# SENTINEL.net
KiCad netlist of a schematic drawn in EAGLE
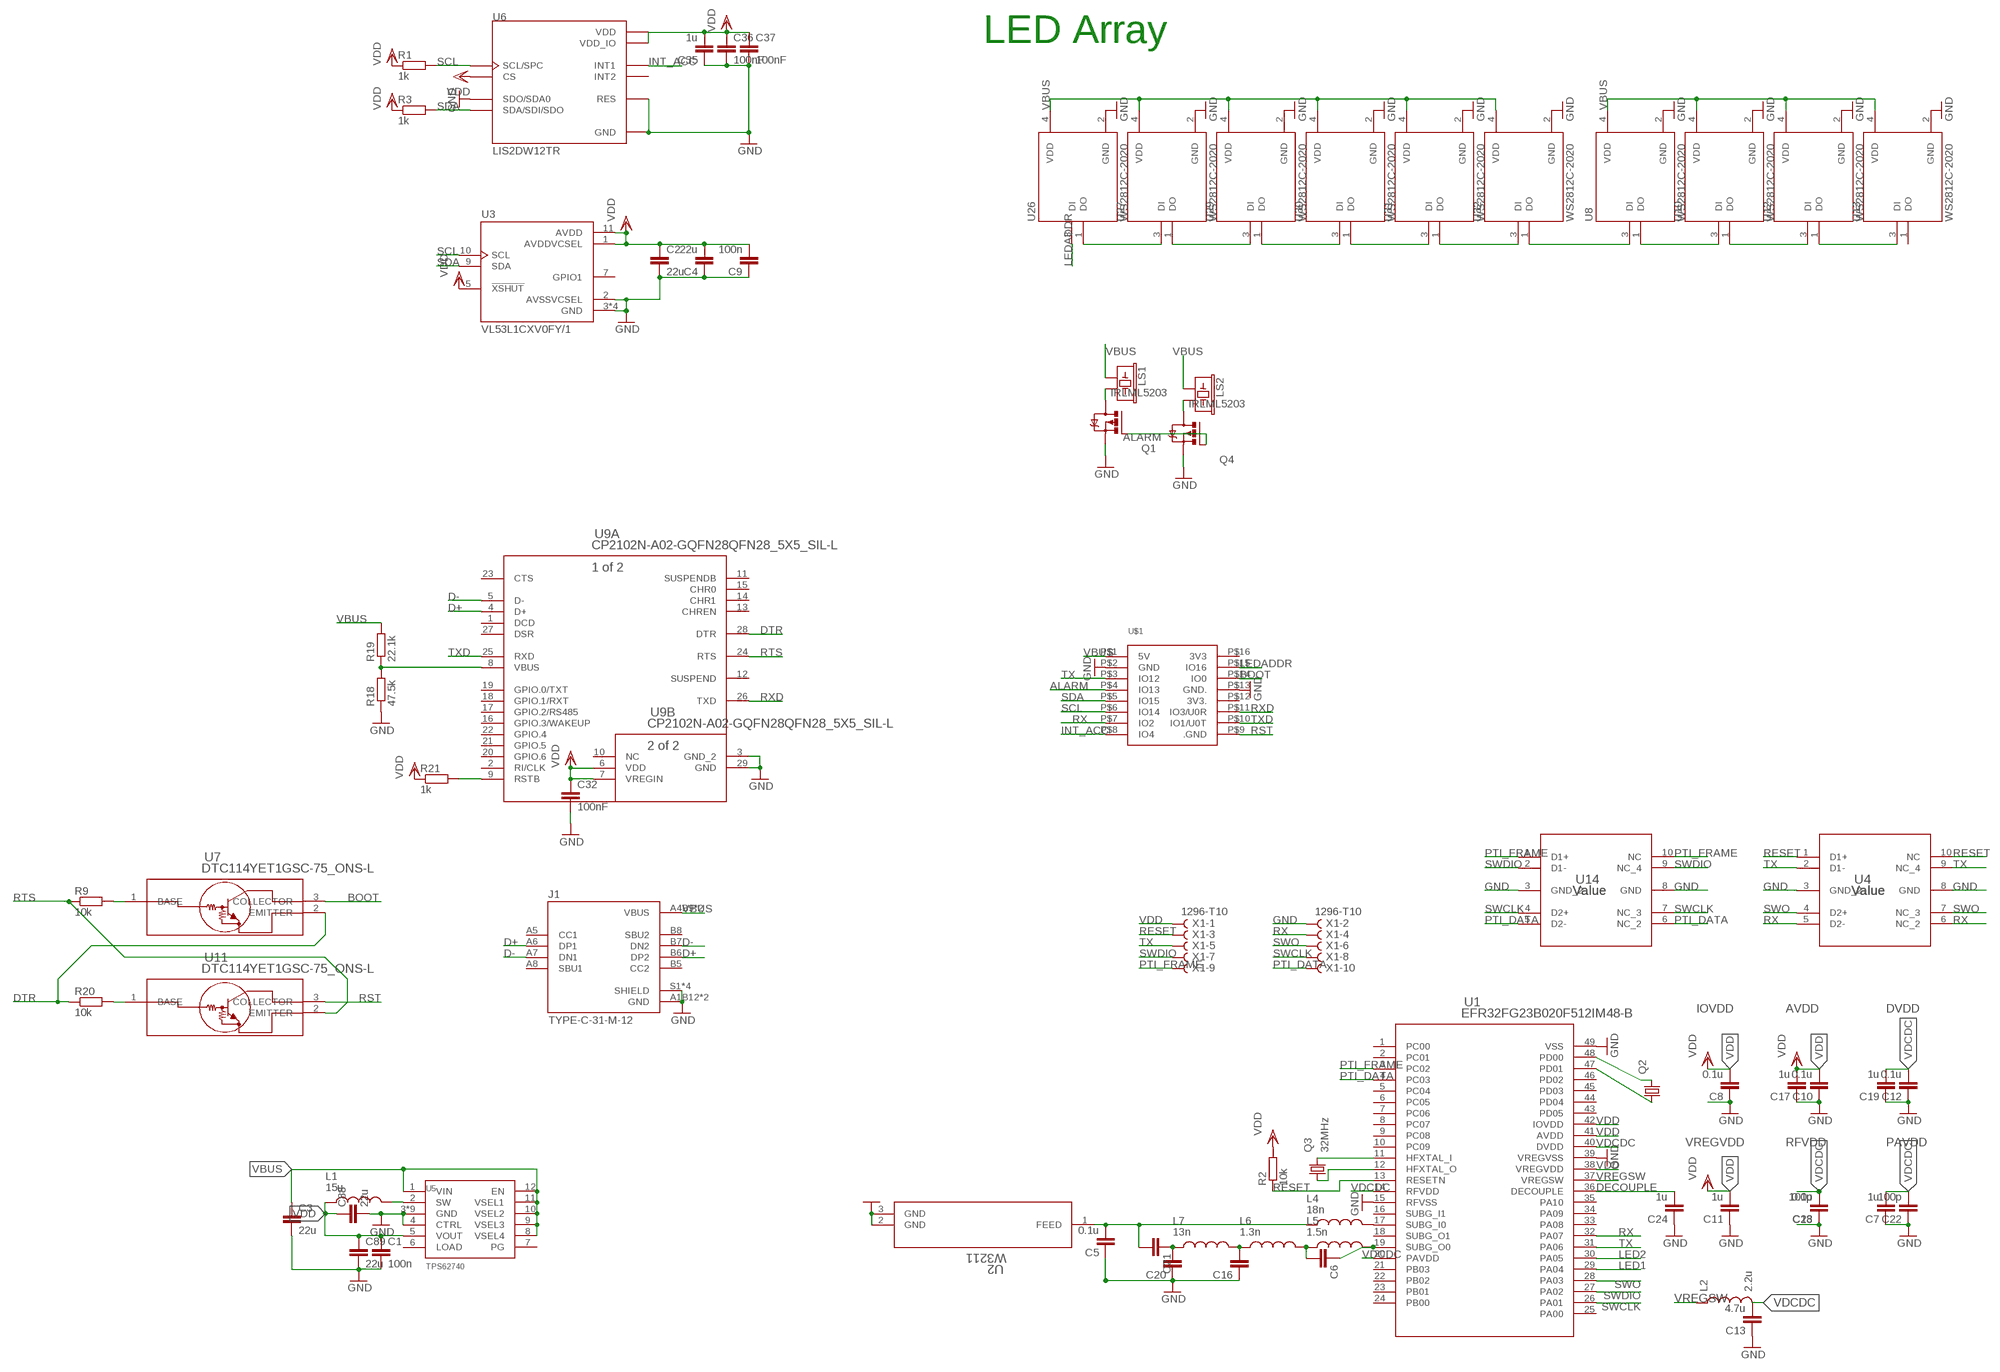
[diagram p0: schematic, sheet 1]

(export (version "E")
  (design (tool "Eeschema 10.0.6"))
  (components
    (comp (ref "C1")
      (value "100n")
      (footprint "eagle-import:C0402")
      (libsource (lib "eagle-import") (part "CC0402"))
    )
    (comp (ref "C2")
      (value "22u")
      (footprint "eagle-import:C0603R")
      (libsource (lib "eagle-import") (part "CC0603R"))
    )
    (comp (ref "C3")
      (value "22u")
      (footprint "eagle-import:C0603R")
      (libsource (lib "eagle-import") (part "CC0603R"))
    )
    (comp (ref "C4")
      (value "22u")
      (footprint "eagle-import:C0603R")
      (libsource (lib "eagle-import") (part "CC0603R"))
    )
    (comp (ref "C5")
      (value "0.1u")
      (footprint "eagle-import:C0402")
      (libsource (lib "eagle-import") (part "CC0402"))
    )
    (comp (ref "C6")
      (value "1.9p")
      (footprint "eagle-import:C0402")
      (libsource (lib "eagle-import") (part "CC0402"))
    )
    (comp (ref "C7")
      (value "1u")
      (footprint "eagle-import:C0402")
      (libsource (lib "eagle-import") (part "CC0402"))
    )
    (comp (ref "C8")
      (value "0.1u")
      (footprint "eagle-import:C0402")
      (libsource (lib "eagle-import") (part "CC0402"))
    )
    (comp (ref "C9")
      (value "100n")
      (footprint "eagle-import:C0402")
      (libsource (lib "eagle-import") (part "CC0402"))
    )
    (comp (ref "C10")
      (value "0.1u")
      (footprint "eagle-import:C0402")
      (libsource (lib "eagle-import") (part "CC0402"))
    )
    (comp (ref "C11")
      (value "1u")
      (footprint "eagle-import:C0402")
      (libsource (lib "eagle-import") (part "CC0402"))
    )
    (comp (ref "C12")
      (value "0.1u")
      (footprint "eagle-import:C0402")
      (libsource (lib "eagle-import") (part "CC0402"))
    )
    (comp (ref "C13")
      (value "4.7u")
      (footprint "eagle-import:C0603R")
      (libsource (lib "eagle-import") (part "CC0603R"))
    )
    (comp (ref "C16")
      (value "7.2p")
      (footprint "eagle-import:C0402")
      (libsource (lib "eagle-import") (part "CC0402"))
    )
    (comp (ref "C17")
      (value "1u")
      (footprint "eagle-import:C0402")
      (libsource (lib "eagle-import") (part "CC0402"))
    )
    (comp (ref "C18")
      (value "0.1u")
      (footprint "eagle-import:C0402")
      (libsource (lib "eagle-import") (part "CC0402"))
    )
    (comp (ref "C19")
      (value "1u")
      (footprint "eagle-import:C0402")
      (libsource (lib "eagle-import") (part "CC0402"))
    )
    (comp (ref "C20")
      (value "1.3p")
      (footprint "eagle-import:C0402")
      (libsource (lib "eagle-import") (part "CC0402"))
    )
    (comp (ref "C21")
      (value "220p")
      (footprint "eagle-import:C0402")
      (libsource (lib "eagle-import") (part "CC0402"))
    )
    (comp (ref "C22")
      (value "100p")
      (footprint "eagle-import:C0402")
      (libsource (lib "eagle-import") (part "CC0402"))
    )
    (comp (ref "C23")
      (value "100p")
      (footprint "eagle-import:C0402")
      (libsource (lib "eagle-import") (part "CC0402"))
    )
    (comp (ref "C24")
      (value "1u")
      (footprint "eagle-import:C0402")
      (libsource (lib "eagle-import") (part "CC0402"))
    )
    (comp (ref "C32")
      (value "100nF")
      (footprint "eagle-import:C0402")
      (libsource (lib "eagle-import") (part "CC0402"))
    )
    (comp (ref "C35")
      (value "1u")
      (footprint "eagle-import:C0603R")
      (libsource (lib "eagle-import") (part "CC0603R"))
    )
    (comp (ref "C36")
      (value "100nF")
      (footprint "eagle-import:C0402")
      (libsource (lib "eagle-import") (part "CC0402"))
    )
    (comp (ref "C37")
      (value "100nF")
      (footprint "eagle-import:C0402")
      (libsource (lib "eagle-import") (part "CC0402"))
    )
    (comp (ref "C88")
      (value "22u")
      (footprint "eagle-import:C0603R")
      (libsource (lib "eagle-import") (part "CC0603R"))
    )
    (comp (ref "C89")
      (value "22u")
      (footprint "eagle-import:C0603R")
      (libsource (lib "eagle-import") (part "CC0603R"))
    )
    (comp (ref "J1")
      (value "TYPE-C-31-M-12")
      (footprint "eagle-import:HRO_TYPE-C-31-M-12")
      (fields (field (name "MF") "HRO Electronics Co., Ltd."))
      (libsource (lib "eagle-import") (part "TYPE-C-31-M-12"))
    )
    (comp (ref "L1")
      (value "15u")
      (footprint "eagle-import:INDC3225X120N")
      (fields (field (name "MF") "Murata") (field (name "MP") "1277AS-H-1R5M=P2"))
      (libsource (lib "eagle-import") (part "1277AS-H-1R5M=P2"))
    )
    (comp (ref "L2")
      (value "2.2u")
      (footprint "eagle-import:L0603")
      (libsource (lib "eagle-import") (part "INDUCTOR"))
    )
    (comp (ref "L4")
      (value "18n")
      (footprint "eagle-import:INDC0402X26N")
      (fields (field (name "MF") "TDK") (field (name "MP") "MHQ0402P7N5JT000"))
      (libsource (lib "eagle-import") (part "MHQ0402P7N5JT000"))
    )
    (comp (ref "L5")
      (value "1.5n")
      (footprint "eagle-import:INDC0402X26N")
      (fields (field (name "MF") "TDK") (field (name "MP") "MHQ0402P7N5JT000"))
      (libsource (lib "eagle-import") (part "MHQ0402P7N5JT000"))
    )
    (comp (ref "L6")
      (value "1.3n")
      (footprint "eagle-import:INDC0402X26N")
      (fields (field (name "MF") "TDK") (field (name "MP") "MHQ0402P7N5JT000"))
      (libsource (lib "eagle-import") (part "MHQ0402P7N5JT000"))
    )
    (comp (ref "L7")
      (value "13n")
      (footprint "eagle-import:INDC0402X26N")
      (fields (field (name "MF") "TDK") (field (name "MP") "MHQ0402P7N5JT000"))
      (libsource (lib "eagle-import") (part "MHQ0402P7N5JT000"))
    )
    (comp (ref "LS1")
      (value "BUZZER-PTH_KIT")
      (footprint "eagle-import:BUZZER-12MM-KIT")
      (libsource (lib "eagle-import") (part "BUZZER-PTH_KIT"))
    )
    (comp (ref "LS2")
      (value "BUZZER-PTH_KIT")
      (footprint "eagle-import:BUZZER-12MM-KIT")
      (libsource (lib "eagle-import") (part "BUZZER-PTH_KIT"))
    )
    (comp (ref "Q1")
      (value "IRLML5203")
      (footprint "eagle-import:MICRO3")
      (libsource (lib "eagle-import") (part "IRLML5203"))
    )
    (comp (ref "Q2")
      (value "KX-327-RT")
      (footprint "eagle-import:2.0X1.2")
      (libsource (lib "eagle-import") (part "KX-327-RT"))
    )
    (comp (ref "Q3")
      (value "32MHz")
      (footprint "eagle-import:2.0X1.6_KX-5")
      (libsource (lib "eagle-import") (part "KX-5"))
    )
    (comp (ref "Q4")
      (value "IRLML5203")
      (footprint "eagle-import:MICRO3")
      (libsource (lib "eagle-import") (part "IRLML5203"))
    )
    (comp (ref "R1")
      (value "1k")
      (footprint "eagle-import:R0402")
      (libsource (lib "eagle-import") (part "RR0402"))
    )
    (comp (ref "R2")
      (value "10k")
      (footprint "eagle-import:R0402")
      (libsource (lib "eagle-import") (part "RR0402"))
    )
    (comp (ref "R3")
      (value "1k")
      (footprint "eagle-import:R0402")
      (libsource (lib "eagle-import") (part "RR0402"))
    )
    (comp (ref "R9")
      (value "10k")
      (footprint "eagle-import:R0402")
      (libsource (lib "eagle-import") (part "RR0402"))
    )
    (comp (ref "R18")
      (value "47.5k")
      (footprint "eagle-import:R0402")
      (libsource (lib "eagle-import") (part "RR0402"))
    )
    (comp (ref "R19")
      (value "22.1k")
      (footprint "eagle-import:R0402")
      (libsource (lib "eagle-import") (part "RR0402"))
    )
    (comp (ref "R20")
      (value "10k")
      (footprint "eagle-import:R0402")
      (libsource (lib "eagle-import") (part "RR0402"))
    )
    (comp (ref "R21")
      (value "1k")
      (footprint "eagle-import:R0402")
      (libsource (lib "eagle-import") (part "RR0402"))
    )
    (comp (ref "U$1")
      (value "ESP32-CAM")
      (footprint "eagle-import:ESP32-CAM")
      (fields (field (name "MF") "AI-Thinker"))
      (libsource (lib "eagle-import") (part "ESP32-CAM"))
    )
    (comp (ref "U1")
      (value "EFR32FG23B020F512IM48-B")
      (footprint "eagle-import:QFN_48_SIL")
      (fields (field (name "COPYRIGHT") "Copyright (C) 2022 Ultra Librarian. All rights reserved."))
      (libsource (lib "eagle-import") (part "EFR32FG23B020F512IM48-B"))
    )
    (comp (ref "U2")
      (value "W3211")
      (footprint "eagle-import:CHIP_3211_PUL")
      (fields (field (name "COPYRIGHT") "Copyright (C) 2022 Ultra Librarian. All rights reserved."))
      (libsource (lib "eagle-import") (part "W3211"))
    )
    (comp (ref "U3")
      (value "VL53L1CXV0FY/1")
      (footprint "eagle-import:SENSOR_VL53L1CXV0FY_1")
      (fields (field (name "MF") "STMicroelectronics"))
      (libsource (lib "eagle-import") (part "VL53L1CXV0FY/1"))
    )
    (comp (ref "U4")
      (value "Value")
      (footprint "eagle-import:DQA0010A")
      (fields (field (name "MANUFACTURER") "Texas Instruments") (field (name "PARTNUMBER") "ESD204DQAR"))
      (libsource (lib "eagle-import") (part "ESD204DQAR"))
    )
    (comp (ref "U5")
      (value "TPS62740")
      (footprint "eagle-import:DSS")
      (libsource (lib "eagle-import") (part "TPS62740"))
    )
    (comp (ref "U6")
      (value "LIS2DW12TR")
      (footprint "eagle-import:LGA12R50P4X4_200X200X70")
      (fields (field (name "MF") "STMicroelectronics"))
      (libsource (lib "eagle-import") (part "LIS2DW12TR"))
    )
    (comp (ref "U7")
      (value "DTC114YET1GSC-75_ONS-L")
      (footprint "eagle-import:SC-75_ONS-L")
      (fields
        (field (name "MANUFACTURER_PART_NUMBER") "DTC114YET1G")
        (field (name "COPYRIGHT") "Copyright (C) 2018 Accelerated Designs. All rights reserved")
      )
      (libsource (lib "eagle-import") (part "DTC114YET1GSC-75_ONS-L"))
    )
    (comp (ref "U8")
      (value "WS2812C-2020")
      (footprint "eagle-import:LED_WS2812C-2020")
      (fields (field (name "MF") "Worldsemi"))
      (libsource (lib "eagle-import") (part "WS2812C-2020"))
    )
    (comp (ref "U9")
      (value "CP2102N-A02-GQFN28QFN28_5X5_SIL-L")
      (footprint "eagle-import:QFN28_5X5_SIL-L")
      (fields
        (field (name "MANUFACTURER_PART_NUMBER") "CP2102N-A02-GQFN28")
        (field (name "COPYRIGHT") "Copyright (C) 2018 Accelerated Designs. All rights reserved")
      )
      (libsource (lib "eagle-import") (part "CP2102N-A02-GQFN28QFN28_5X5_SIL-L"))
    )
    (comp (ref "U10")
      (value "WS2812C-2020")
      (footprint "eagle-import:LED_WS2812C-2020")
      (fields (field (name "MF") "Worldsemi"))
      (libsource (lib "eagle-import") (part "WS2812C-2020"))
    )
    (comp (ref "U11")
      (value "DTC114YET1GSC-75_ONS-L")
      (footprint "eagle-import:SC-75_ONS-L")
      (fields
        (field (name "MANUFACTURER_PART_NUMBER") "DTC114YET1G")
        (field (name "COPYRIGHT") "Copyright (C) 2018 Accelerated Designs. All rights reserved")
      )
      (libsource (lib "eagle-import") (part "DTC114YET1GSC-75_ONS-L"))
    )
    (comp (ref "U12")
      (value "WS2812C-2020")
      (footprint "eagle-import:LED_WS2812C-2020")
      (fields (field (name "MF") "Worldsemi"))
      (libsource (lib "eagle-import") (part "WS2812C-2020"))
    )
    (comp (ref "U13")
      (value "WS2812C-2020")
      (footprint "eagle-import:LED_WS2812C-2020")
      (fields (field (name "MF") "Worldsemi"))
      (libsource (lib "eagle-import") (part "WS2812C-2020"))
    )
    (comp (ref "U14")
      (value "Value")
      (footprint "eagle-import:DQA0010A")
      (fields (field (name "MANUFACTURER") "Texas Instruments") (field (name "PARTNUMBER") "ESD204DQAR"))
      (libsource (lib "eagle-import") (part "ESD204DQAR"))
    )
    (comp (ref "U26")
      (value "WS2812C-2020")
      (footprint "eagle-import:LED_WS2812C-2020")
      (fields (field (name "MF") "Worldsemi"))
      (libsource (lib "eagle-import") (part "WS2812C-2020"))
    )
    (comp (ref "U27")
      (value "WS2812C-2020")
      (footprint "eagle-import:LED_WS2812C-2020")
      (fields (field (name "MF") "Worldsemi"))
      (libsource (lib "eagle-import") (part "WS2812C-2020"))
    )
    (comp (ref "U29")
      (value "WS2812C-2020")
      (footprint "eagle-import:LED_WS2812C-2020")
      (fields (field (name "MF") "Worldsemi"))
      (libsource (lib "eagle-import") (part "WS2812C-2020"))
    )
    (comp (ref "U30")
      (value "WS2812C-2020")
      (footprint "eagle-import:LED_WS2812C-2020")
      (fields (field (name "MF") "Worldsemi"))
      (libsource (lib "eagle-import") (part "WS2812C-2020"))
    )
    (comp (ref "U31")
      (value "WS2812C-2020")
      (footprint "eagle-import:LED_WS2812C-2020")
      (fields (field (name "MF") "Worldsemi"))
      (libsource (lib "eagle-import") (part "WS2812C-2020"))
    )
    (comp (ref "U32")
      (value "WS2812C-2020")
      (footprint "eagle-import:LED_WS2812C-2020")
      (fields (field (name "MF") "Worldsemi"))
      (libsource (lib "eagle-import") (part "WS2812C-2020"))
    )
    (comp (ref "X1")
      (value "1296-T10")
      (footprint "eagle-import:1296-10")
      (libsource (lib "eagle-import") (part "1296-T10"))
    )
  )
  (nets
    (net (code "1") (name "/ALARM") (class "Default")
      (node (ref "Q1") (pin "1") (pinfunction "G_1") (pintype "passive"))
      (node (ref "Q4") (pin "1") (pinfunction "G_1") (pintype "passive"))
      (node (ref "U$1") (pin "P$4") (pinfunction "IO13_P$4") (pintype "bidirectional"))
    )
    (net (code "2") (name "/BOOT") (class "Default")
      (node (ref "U$1") (pin "P$14") (pinfunction "IO0_P$14") (pintype "bidirectional"))
      (node (ref "U7") (pin "3") (pinfunction "COLLECTOR_3") (pintype "output"))
    )
    (net (code "3") (name "/D+") (class "Default")
      (node (ref "J1") (pin "A6") (pinfunction "DP1_A6") (pintype "bidirectional"))
      (node (ref "J1") (pin "B6") (pinfunction "DP2_B6") (pintype "bidirectional"))
      (node (ref "U9") (pin "4") (pinfunction "D+_4") (pintype "input"))
    )
    (net (code "4") (name "/D-") (class "Default")
      (node (ref "J1") (pin "A7") (pinfunction "DN1_A7") (pintype "bidirectional"))
      (node (ref "J1") (pin "B7") (pinfunction "DN2_B7") (pintype "bidirectional"))
      (node (ref "U9") (pin "5") (pinfunction "D-_5") (pintype "input"))
    )
    (net (code "5") (name "/DECOUPLE") (class "Default")
      (node (ref "C24") (pin "2") (pinfunction "2_2") (pintype "passive"))
      (node (ref "U1") (pin "36") (pinfunction "DECOUPLE_36") (pintype "passive"))
    )
    (net (code "6") (name "/DTR") (class "Default")
      (node (ref "R20") (pin "1") (pinfunction "1_1") (pintype "passive"))
      (node (ref "U7") (pin "2") (pinfunction "EMITTER_2") (pintype "passive"))
      (node (ref "U9") (pin "28") (pinfunction "DTR_28") (pintype "output"))
    )
    (net (code "7") (name "/INT_ACC") (class "Default")
      (node (ref "U$1") (pin "P$8") (pinfunction "IO4_P$8") (pintype "bidirectional"))
      (node (ref "U6") (pin "12") (pinfunction "INT1_12") (pintype "output"))
    )
    (net (code "8") (name "/LED1") (class "Default")
      (node (ref "U1") (pin "29") (pinfunction "PA04_29") (pintype "bidirectional"))
    )
    (net (code "9") (name "/LED2") (class "Default")
      (node (ref "U1") (pin "30") (pinfunction "PA05_30") (pintype "bidirectional"))
    )
    (net (code "10") (name "/LEDADDR") (class "Default")
      (node (ref "U$1") (pin "P$15") (pinfunction "IO16_P$15") (pintype "bidirectional"))
      (node (ref "U26") (pin "3") (pinfunction "DI_3") (pintype "input"))
    )
    (net (code "11") (name "/PTI_DATA") (class "Default")
      (node (ref "U1") (pin "4") (pinfunction "PC03_4") (pintype "bidirectional"))
      (node (ref "U14") (pin "5") (pinfunction "D2-_5") (pintype "bidirectional"))
      (node (ref "U14") (pin "6") (pinfunction "NC_2_6") (pintype "passive"))
      (node (ref "X1") (pin "10") (pinfunction "B_10") (pintype "passive"))
    )
    (net (code "12") (name "/PTI_FRAME") (class "Default")
      (node (ref "U1") (pin "3") (pinfunction "PC02_3") (pintype "bidirectional"))
      (node (ref "U14") (pin "1") (pinfunction "D1+_1") (pintype "bidirectional"))
      (node (ref "U14") (pin "10") (pinfunction "NC_10") (pintype "passive"))
      (node (ref "X1") (pin "9") (pinfunction "B_9") (pintype "passive"))
    )
    (net (code "13") (name "/RESET") (class "Default")
      (node (ref "R2") (pin "1") (pinfunction "1_1") (pintype "passive"))
      (node (ref "U1") (pin "13") (pinfunction "RESETN_13") (pintype "input"))
      (node (ref "U4") (pin "1") (pinfunction "D1+_1") (pintype "bidirectional"))
      (node (ref "U4") (pin "10") (pinfunction "NC_10") (pintype "passive"))
      (node (ref "X1") (pin "3") (pinfunction "B_3") (pintype "passive"))
    )
    (net (code "14") (name "/RST") (class "Default")
      (node (ref "U$1") (pin "P$9") (pinfunction ".GND_P$9") (pintype "bidirectional"))
      (node (ref "U11") (pin "3") (pinfunction "COLLECTOR_3") (pintype "output"))
    )
    (net (code "15") (name "/RTS") (class "Default")
      (node (ref "R9") (pin "1") (pinfunction "1_1") (pintype "passive"))
      (node (ref "U11") (pin "2") (pinfunction "EMITTER_2") (pintype "passive"))
      (node (ref "U9") (pin "24") (pinfunction "RTS_24") (pintype "output"))
    )
    (net (code "16") (name "/RX") (class "Default")
      (node (ref "U$1") (pin "P$7") (pinfunction "IO2_P$7") (pintype "bidirectional"))
      (node (ref "U1") (pin "32") (pinfunction "PA07_32") (pintype "bidirectional"))
      (node (ref "U4") (pin "5") (pinfunction "D2-_5") (pintype "bidirectional"))
      (node (ref "U4") (pin "6") (pinfunction "NC_2_6") (pintype "passive"))
      (node (ref "X1") (pin "4") (pinfunction "B_4") (pintype "passive"))
    )
    (net (code "17") (name "/RXD") (class "Default")
      (node (ref "U$1") (pin "P$11") (pinfunction "IO3/U0R_P$11") (pintype "bidirectional"))
      (node (ref "U9") (pin "26") (pinfunction "TXD_26") (pintype "output"))
    )
    (net (code "18") (name "/SCL") (class "Default")
      (node (ref "R1") (pin "2") (pinfunction "2_2") (pintype "passive"))
      (node (ref "U$1") (pin "P$6") (pinfunction "IO14_P$6") (pintype "bidirectional"))
      (node (ref "U3") (pin "10") (pinfunction "SCL_10") (pintype "input"))
      (node (ref "U6") (pin "1") (pinfunction "SCL/SPC_1") (pintype "input"))
    )
    (net (code "19") (name "/SDA") (class "Default")
      (node (ref "R3") (pin "2") (pinfunction "2_2") (pintype "passive"))
      (node (ref "U$1") (pin "P$5") (pinfunction "IO15_P$5") (pintype "bidirectional"))
      (node (ref "U3") (pin "9") (pinfunction "SDA_9") (pintype "bidirectional"))
      (node (ref "U6") (pin "4") (pinfunction "SDA/SDI/SDO_4") (pintype "bidirectional"))
    )
    (net (code "20") (name "/SWCLK") (class "Default")
      (node (ref "U1") (pin "26") (pinfunction "PA01_26") (pintype "bidirectional"))
      (node (ref "U14") (pin "4") (pinfunction "D2+_4") (pintype "bidirectional"))
      (node (ref "U14") (pin "7") (pinfunction "NC_3_7") (pintype "passive"))
      (node (ref "X1") (pin "8") (pinfunction "B_8") (pintype "passive"))
    )
    (net (code "21") (name "/SWDIO") (class "Default")
      (node (ref "U1") (pin "27") (pinfunction "PA02_27") (pintype "bidirectional"))
      (node (ref "U14") (pin "2") (pinfunction "D1-_2") (pintype "bidirectional"))
      (node (ref "U14") (pin "9") (pinfunction "NC_4_9") (pintype "passive"))
      (node (ref "X1") (pin "7") (pinfunction "B_7") (pintype "passive"))
    )
    (net (code "22") (name "/SWO") (class "Default")
      (node (ref "U1") (pin "28") (pinfunction "PA03_28") (pintype "bidirectional"))
      (node (ref "U4") (pin "4") (pinfunction "D2+_4") (pintype "bidirectional"))
      (node (ref "U4") (pin "7") (pinfunction "NC_3_7") (pintype "passive"))
      (node (ref "X1") (pin "6") (pinfunction "B_6") (pintype "passive"))
    )
    (net (code "23") (name "/TX") (class "Default")
      (node (ref "U$1") (pin "P$3") (pinfunction "IO12_P$3") (pintype "bidirectional"))
      (node (ref "U1") (pin "31") (pinfunction "PA06_31") (pintype "bidirectional"))
      (node (ref "U4") (pin "2") (pinfunction "D1-_2") (pintype "bidirectional"))
      (node (ref "U4") (pin "9") (pinfunction "NC_4_9") (pintype "passive"))
      (node (ref "X1") (pin "5") (pinfunction "B_5") (pintype "passive"))
    )
    (net (code "24") (name "/TXD") (class "Default")
      (node (ref "U$1") (pin "P$10") (pinfunction "IO1/U0T_P$10") (pintype "bidirectional"))
      (node (ref "U9") (pin "25") (pinfunction "RXD_25") (pintype "input"))
    )
    (net (code "25") (name "/VREGSW") (class "Default")
      (node (ref "L2") (pin "1") (pinfunction "1_1") (pintype "passive"))
      (node (ref "U1") (pin "37") (pinfunction "VREGSW_37") (pintype "power_in"))
    )
    (net (code "26") (name "GND") (class "Default")
      (node (ref "C1") (pin "2") (pinfunction "2_2") (pintype "passive"))
      (node (ref "C10") (pin "1") (pinfunction "1_1") (pintype "passive"))
      (node (ref "C11") (pin "1") (pinfunction "1_1") (pintype "passive"))
      (node (ref "C12") (pin "1") (pinfunction "1_1") (pintype "passive"))
      (node (ref "C13") (pin "1") (pinfunction "1_1") (pintype "passive"))
      (node (ref "C16") (pin "1") (pinfunction "1_1") (pintype "passive"))
      (node (ref "C17") (pin "1") (pinfunction "1_1") (pintype "passive"))
      (node (ref "C18") (pin "1") (pinfunction "1_1") (pintype "passive"))
      (node (ref "C19") (pin "1") (pinfunction "1_1") (pintype "passive"))
      (node (ref "C2") (pin "2") (pinfunction "2_2") (pintype "passive"))
      (node (ref "C20") (pin "1") (pinfunction "1_1") (pintype "passive"))
      (node (ref "C22") (pin "1") (pinfunction "1_1") (pintype "passive"))
      (node (ref "C23") (pin "1") (pinfunction "1_1") (pintype "passive"))
      (node (ref "C24") (pin "1") (pinfunction "1_1") (pintype "passive"))
      (node (ref "C3") (pin "2") (pinfunction "2_2") (pintype "passive"))
      (node (ref "C32") (pin "2") (pinfunction "2_2") (pintype "passive"))
      (node (ref "C35") (pin "1") (pinfunction "1_1") (pintype "passive"))
      (node (ref "C36") (pin "2") (pinfunction "2_2") (pintype "passive"))
      (node (ref "C37") (pin "2") (pinfunction "2_2") (pintype "passive"))
      (node (ref "C4") (pin "1") (pinfunction "1_1") (pintype "passive"))
      (node (ref "C5") (pin "1") (pinfunction "1_1") (pintype "passive"))
      (node (ref "C7") (pin "1") (pinfunction "1_1") (pintype "passive"))
      (node (ref "C8") (pin "1") (pinfunction "1_1") (pintype "passive"))
      (node (ref "C88") (pin "2") (pinfunction "2_2") (pintype "passive"))
      (node (ref "C89") (pin "2") (pinfunction "2_2") (pintype "passive"))
      (node (ref "C9") (pin "1") (pinfunction "1_1") (pintype "passive"))
      (node (ref "J1") (pin "A1B12") (pinfunction "GND_A1B12") (pintype "power_in"))
      (node (ref "J1") (pin "B1A12") (pinfunction "GND_B1A12") (pintype "power_in"))
      (node (ref "J1") (pin "S1") (pinfunction "SHIELD_S1") (pintype "passive"))
      (node (ref "J1") (pin "S2") (pinfunction "SHIELD_S2") (pintype "passive"))
      (node (ref "J1") (pin "S3") (pinfunction "SHIELD_S3") (pintype "passive"))
      (node (ref "J1") (pin "S4") (pinfunction "SHIELD_S4") (pintype "passive"))
      (node (ref "Q1") (pin "2") (pinfunction "S_2") (pintype "passive"))
      (node (ref "Q4") (pin "2") (pinfunction "S_2") (pintype "passive"))
      (node (ref "R18") (pin "1") (pinfunction "1_1") (pintype "passive"))
      (node (ref "U$1") (pin "P$13") (pinfunction "GND._P$13") (pintype "bidirectional"))
      (node (ref "U$1") (pin "P$2") (pinfunction "GND_P$2") (pintype "bidirectional"))
      (node (ref "U1") (pin "15") (pinfunction "RFVSS_15") (pintype "power_in"))
      (node (ref "U1") (pin "39") (pinfunction "VREGVSS_39") (pintype "power_in"))
      (node (ref "U1") (pin "49") (pinfunction "VSS_49") (pintype "power_in"))
      (node (ref "U10") (pin "2") (pinfunction "GND_2") (pintype "power_in"))
      (node (ref "U12") (pin "2") (pinfunction "GND_2") (pintype "power_in"))
      (node (ref "U13") (pin "2") (pinfunction "GND_2") (pintype "power_in"))
      (node (ref "U14") (pin "3") (pinfunction "GND_2_3") (pintype "power_in"))
      (node (ref "U14") (pin "8") (pinfunction "GND_8") (pintype "power_in"))
      (node (ref "U2") (pin "2") (pinfunction "GND_2") (pintype "passive"))
      (node (ref "U2") (pin "3") (pinfunction "GND_3") (pintype "passive"))
      (node (ref "U26") (pin "2") (pinfunction "GND_2") (pintype "power_in"))
      (node (ref "U27") (pin "2") (pinfunction "GND_2") (pintype "power_in"))
      (node (ref "U29") (pin "2") (pinfunction "GND_2") (pintype "power_in"))
      (node (ref "U3") (pin "12") (pinfunction "GND_12") (pintype "power_in"))
      (node (ref "U3") (pin "2") (pinfunction "AVSSVCSEL_2") (pintype "power_in"))
      (node (ref "U3") (pin "3") (pinfunction "GND_3") (pintype "power_in"))
      (node (ref "U3") (pin "4") (pinfunction "GND_4") (pintype "power_in"))
      (node (ref "U3") (pin "6") (pinfunction "GND_6") (pintype "power_in"))
      (node (ref "U30") (pin "2") (pinfunction "GND_2") (pintype "power_in"))
      (node (ref "U31") (pin "2") (pinfunction "GND_2") (pintype "power_in"))
      (node (ref "U32") (pin "2") (pinfunction "GND_2") (pintype "power_in"))
      (node (ref "U4") (pin "3") (pinfunction "GND_2_3") (pintype "power_in"))
      (node (ref "U4") (pin "8") (pinfunction "GND_8") (pintype "power_in"))
      (node (ref "U5") (pin "13") (pinfunction "GND_13") (pintype "bidirectional"))
      (node (ref "U5") (pin "14") (pinfunction "GND_14") (pintype "bidirectional"))
      (node (ref "U5") (pin "15") (pinfunction "GND_15") (pintype "bidirectional"))
      (node (ref "U5") (pin "16") (pinfunction "GND_16") (pintype "bidirectional"))
      (node (ref "U5") (pin "18") (pinfunction "GND_18") (pintype "bidirectional"))
      (node (ref "U5") (pin "19") (pinfunction "GND_19") (pintype "bidirectional"))
      (node (ref "U5") (pin "20") (pinfunction "GND_20") (pintype "bidirectional"))
      (node (ref "U5") (pin "3") (pinfunction "GND_3") (pintype "bidirectional"))
      (node (ref "U5") (pin "4") (pinfunction "CTRL_4") (pintype "bidirectional"))
      (node (ref "U5") (pin "P$18") (pinfunction "GND_P$18") (pintype "bidirectional"))
      (node (ref "U6") (pin "3") (pinfunction "SDO/SDA0_3") (pintype "bidirectional"))
      (node (ref "U6") (pin "6") (pinfunction "GND_6") (pintype "power_in"))
      (node (ref "U6") (pin "7") (pinfunction "RES_7") (pintype "passive"))
      (node (ref "U6") (pin "8") (pinfunction "GND_8") (pintype "power_in"))
      (node (ref "U8") (pin "2") (pinfunction "GND_2") (pintype "power_in"))
      (node (ref "U9") (pin "29") (pinfunction "GND_29") (pintype "passive"))
      (node (ref "U9") (pin "3") (pinfunction "GND_2_3") (pintype "passive"))
      (node (ref "X1") (pin "2") (pinfunction "B_2") (pintype "passive"))
    )
    (net (code "27") (name "Net-(C6-Pad2)") (class "Default")
      (node (ref "C6") (pin "2") (pinfunction "2_2") (pintype "passive"))
      (node (ref "L5") (pin "1") (pinfunction "1_1") (pintype "passive"))
      (node (ref "L6") (pin "2") (pinfunction "2_2") (pintype "passive"))
    )
    (net (code "28") (name "Net-(C16-Pad2)") (class "Default")
      (node (ref "C16") (pin "2") (pinfunction "2_2") (pintype "passive"))
      (node (ref "L6") (pin "1") (pinfunction "1_1") (pintype "passive"))
      (node (ref "L7") (pin "2") (pinfunction "2_2") (pintype "passive"))
    )
    (net (code "29") (name "Net-(C20-Pad2)") (class "Default")
      (node (ref "C20") (pin "2") (pinfunction "2_2") (pintype "passive"))
      (node (ref "C21") (pin "1") (pinfunction "1_1") (pintype "passive"))
      (node (ref "L7") (pin "1") (pinfunction "1_1") (pintype "passive"))
    )
    (net (code "30") (name "Net-(LS1-2)") (class "Default")
      (node (ref "LS1") (pin "-") (pinfunction "2_-") (pintype "passive"))
      (node (ref "Q1") (pin "3") (pinfunction "D_3") (pintype "passive"))
    )
    (net (code "31") (name "Net-(LS2-2)") (class "Default")
      (node (ref "LS2") (pin "-") (pinfunction "2_-") (pintype "passive"))
      (node (ref "Q4") (pin "3") (pinfunction "D_3") (pintype "passive"))
    )
    (net (code "32") (name "Net-(Q3-2)") (class "Default")
      (node (ref "Q3") (pin "3") (pinfunction "2_3") (pintype "passive"))
      (node (ref "U1") (pin "11") (pinfunction "HFXTAL_I_11") (pintype "input"))
    )
    (net (code "33") (name "Net-(U1-HFXTAL_O)") (class "Default")
      (node (ref "Q3") (pin "1") (pinfunction "1_1") (pintype "passive"))
      (node (ref "U1") (pin "12") (pinfunction "HFXTAL_O_12") (pintype "output"))
    )
    (net (code "34") (name "Net-(U1-PD00)") (class "Default")
      (node (ref "Q2") (pin "2") (pinfunction "2_2") (pintype "passive"))
      (node (ref "U1") (pin "48") (pinfunction "PD00_48") (pintype "bidirectional"))
    )
    (net (code "35") (name "Net-(U1-PD01)") (class "Default")
      (node (ref "Q2") (pin "1") (pinfunction "1_1") (pintype "passive"))
      (node (ref "U1") (pin "47") (pinfunction "PD01_47") (pintype "bidirectional"))
    )
    (net (code "36") (name "Net-(U1-SUBG_I0)") (class "Default")
      (node (ref "L4") (pin "2") (pinfunction "2_2") (pintype "passive"))
      (node (ref "U1") (pin "17") (pinfunction "SUBG_I0_17") (pintype "input"))
    )
    (net (code "37") (name "Net-(U1-SUBG_O0)") (class "Default")
      (node (ref "C6") (pin "1") (pinfunction "1_1") (pintype "passive"))
      (node (ref "L5") (pin "2") (pinfunction "2_2") (pintype "passive"))
      (node (ref "U1") (pin "19") (pinfunction "SUBG_O0_19") (pintype "output"))
    )
    (net (code "38") (name "Net-(U2-FEED)") (class "Default")
      (node (ref "C21") (pin "2") (pinfunction "2_2") (pintype "passive"))
      (node (ref "C5") (pin "2") (pinfunction "2_2") (pintype "passive"))
      (node (ref "L4") (pin "1") (pinfunction "1_1") (pintype "passive"))
      (node (ref "U2") (pin "1") (pinfunction "FEED_1") (pintype "passive"))
    )
    (net (code "39") (name "Net-(U5-SW)") (class "Default")
      (node (ref "L1") (pin "2") (pinfunction "2_2") (pintype "passive"))
      (node (ref "U5") (pin "2") (pinfunction "SW_2") (pintype "bidirectional"))
    )
    (net (code "40") (name "Net-(U7-BASE)") (class "Default")
      (node (ref "R9") (pin "2") (pinfunction "2_2") (pintype "passive"))
      (node (ref "U7") (pin "1") (pinfunction "BASE_1") (pintype "input"))
    )
    (net (code "41") (name "Net-(U9A-RSTB)") (class "Default")
      (node (ref "R21") (pin "2") (pinfunction "2_2") (pintype "passive"))
      (node (ref "U9") (pin "9") (pinfunction "RSTB_9") (pintype "passive"))
    )
    (net (code "42") (name "Net-(U9A-VBUS)") (class "Default")
      (node (ref "R18") (pin "2") (pinfunction "2_2") (pintype "passive"))
      (node (ref "R19") (pin "1") (pinfunction "1_1") (pintype "passive"))
      (node (ref "U9") (pin "8") (pinfunction "VBUS_8") (pintype "input"))
    )
    (net (code "43") (name "Net-(U10-DI)") (class "Default")
      (node (ref "U10") (pin "3") (pinfunction "DI_3") (pintype "input"))
      (node (ref "U8") (pin "1") (pinfunction "DO_1") (pintype "output"))
    )
    (net (code "44") (name "Net-(U10-DO)") (class "Default")
      (node (ref "U10") (pin "1") (pinfunction "DO_1") (pintype "output"))
      (node (ref "U12") (pin "3") (pinfunction "DI_3") (pintype "input"))
    )
    (net (code "45") (name "Net-(U11-BASE)") (class "Default")
      (node (ref "R20") (pin "2") (pinfunction "2_2") (pintype "passive"))
      (node (ref "U11") (pin "1") (pinfunction "BASE_1") (pintype "input"))
    )
    (net (code "46") (name "Net-(U12-DO)") (class "Default")
      (node (ref "U12") (pin "1") (pinfunction "DO_1") (pintype "output"))
      (node (ref "U13") (pin "3") (pinfunction "DI_3") (pintype "input"))
    )
    (net (code "47") (name "Net-(U26-DO)") (class "Default")
      (node (ref "U26") (pin "1") (pinfunction "DO_1") (pintype "output"))
      (node (ref "U27") (pin "3") (pinfunction "DI_3") (pintype "input"))
    )
    (net (code "48") (name "Net-(U27-DO)") (class "Default")
      (node (ref "U27") (pin "1") (pinfunction "DO_1") (pintype "output"))
      (node (ref "U29") (pin "3") (pinfunction "DI_3") (pintype "input"))
    )
    (net (code "49") (name "Net-(U29-DO)") (class "Default")
      (node (ref "U29") (pin "1") (pinfunction "DO_1") (pintype "output"))
      (node (ref "U30") (pin "3") (pinfunction "DI_3") (pintype "input"))
    )
    (net (code "50") (name "Net-(U30-DO)") (class "Default")
      (node (ref "U30") (pin "1") (pinfunction "DO_1") (pintype "output"))
      (node (ref "U31") (pin "3") (pinfunction "DI_3") (pintype "input"))
    )
    (net (code "51") (name "Net-(U31-DO)") (class "Default")
      (node (ref "U31") (pin "1") (pinfunction "DO_1") (pintype "output"))
      (node (ref "U32") (pin "3") (pinfunction "DI_3") (pintype "input"))
    )
    (net (code "52") (name "Net-(U32-DO)") (class "Default")
      (node (ref "U32") (pin "1") (pinfunction "DO_1") (pintype "output"))
      (node (ref "U8") (pin "3") (pinfunction "DI_3") (pintype "input"))
    )
    (net (code "53") (name "VBUS") (class "Default")
      (node (ref "C3") (pin "1") (pinfunction "1_1") (pintype "passive"))
      (node (ref "J1") (pin "A4B9") (pinfunction "VBUS_A4B9") (pintype "power_in"))
      (node (ref "J1") (pin "B4A9") (pinfunction "VBUS_B4A9") (pintype "power_in"))
      (node (ref "LS1") (pin "+") (pinfunction "1_+") (pintype "passive"))
      (node (ref "LS2") (pin "+") (pinfunction "1_+") (pintype "passive"))
      (node (ref "R19") (pin "2") (pinfunction "2_2") (pintype "passive"))
      (node (ref "U$1") (pin "P$1") (pinfunction "5V_P$1") (pintype "bidirectional"))
      (node (ref "U10") (pin "4") (pinfunction "VDD_4") (pintype "power_in"))
      (node (ref "U12") (pin "4") (pinfunction "VDD_4") (pintype "power_in"))
      (node (ref "U13") (pin "4") (pinfunction "VDD_4") (pintype "power_in"))
      (node (ref "U26") (pin "4") (pinfunction "VDD_4") (pintype "power_in"))
      (node (ref "U27") (pin "4") (pinfunction "VDD_4") (pintype "power_in"))
      (node (ref "U29") (pin "4") (pinfunction "VDD_4") (pintype "power_in"))
      (node (ref "U30") (pin "4") (pinfunction "VDD_4") (pintype "power_in"))
      (node (ref "U31") (pin "4") (pinfunction "VDD_4") (pintype "power_in"))
      (node (ref "U32") (pin "4") (pinfunction "VDD_4") (pintype "power_in"))
      (node (ref "U5") (pin "1") (pinfunction "VIN_1") (pintype "bidirectional"))
      (node (ref "U5") (pin "10") (pinfunction "VSEL2_10") (pintype "bidirectional"))
      (node (ref "U5") (pin "11") (pinfunction "VSEL1_11") (pintype "bidirectional"))
      (node (ref "U5") (pin "12") (pinfunction "EN_12") (pintype "bidirectional"))
      (node (ref "U5") (pin "8") (pinfunction "VSEL4_8") (pintype "bidirectional"))
      (node (ref "U5") (pin "9") (pinfunction "VSEL3_9") (pintype "bidirectional"))
      (node (ref "U8") (pin "4") (pinfunction "VDD_4") (pintype "power_in"))
    )
    (net (code "54") (name "VDCDC") (class "Default")
      (node (ref "C12") (pin "2") (pinfunction "2_2") (pintype "passive"))
      (node (ref "C13") (pin "2") (pinfunction "2_2") (pintype "passive"))
      (node (ref "C18") (pin "2") (pinfunction "2_2") (pintype "passive"))
      (node (ref "C19") (pin "2") (pinfunction "2_2") (pintype "passive"))
      (node (ref "C22") (pin "2") (pinfunction "2_2") (pintype "passive"))
      (node (ref "C23") (pin "2") (pinfunction "2_2") (pintype "passive"))
      (node (ref "C7") (pin "2") (pinfunction "2_2") (pintype "passive"))
      (node (ref "L2") (pin "2") (pinfunction "2_2") (pintype "passive"))
      (node (ref "U1") (pin "14") (pinfunction "RFVDD_14") (pintype "power_in"))
      (node (ref "U1") (pin "20") (pinfunction "PAVDD_20") (pintype "power_in"))
      (node (ref "U1") (pin "40") (pinfunction "DVDD_40") (pintype "power_in"))
    )
    (net (code "55") (name "VDD") (class "Default")
      (node (ref "C1") (pin "1") (pinfunction "1_1") (pintype "passive"))
      (node (ref "C10") (pin "2") (pinfunction "2_2") (pintype "passive"))
      (node (ref "C11") (pin "2") (pinfunction "2_2") (pintype "passive"))
      (node (ref "C17") (pin "2") (pinfunction "2_2") (pintype "passive"))
      (node (ref "C2") (pin "1") (pinfunction "1_1") (pintype "passive"))
      (node (ref "C32") (pin "1") (pinfunction "1_1") (pintype "passive"))
      (node (ref "C35") (pin "2") (pinfunction "2_2") (pintype "passive"))
      (node (ref "C36") (pin "1") (pinfunction "1_1") (pintype "passive"))
      (node (ref "C37") (pin "1") (pinfunction "1_1") (pintype "passive"))
      (node (ref "C4") (pin "2") (pinfunction "2_2") (pintype "passive"))
      (node (ref "C8") (pin "2") (pinfunction "2_2") (pintype "passive"))
      (node (ref "C88") (pin "1") (pinfunction "1_1") (pintype "passive"))
      (node (ref "C89") (pin "1") (pinfunction "1_1") (pintype "passive"))
      (node (ref "C9") (pin "2") (pinfunction "2_2") (pintype "passive"))
      (node (ref "L1") (pin "1") (pinfunction "1_1") (pintype "passive"))
      (node (ref "R1") (pin "1") (pinfunction "1_1") (pintype "passive"))
      (node (ref "R2") (pin "2") (pinfunction "2_2") (pintype "passive"))
      (node (ref "R21") (pin "1") (pinfunction "1_1") (pintype "passive"))
      (node (ref "R3") (pin "1") (pinfunction "1_1") (pintype "passive"))
      (node (ref "U1") (pin "38") (pinfunction "VREGVDD_38") (pintype "power_in"))
      (node (ref "U1") (pin "41") (pinfunction "AVDD_41") (pintype "power_in"))
      (node (ref "U1") (pin "42") (pinfunction "IOVDD_42") (pintype "power_in"))
      (node (ref "U3") (pin "1") (pinfunction "AVDDVCSEL_1") (pintype "power_in"))
      (node (ref "U3") (pin "11") (pinfunction "AVDD_11") (pintype "power_in"))
      (node (ref "U3") (pin "5") (pinfunction "~{XSHUT}_5") (pintype "input"))
      (node (ref "U5") (pin "5") (pinfunction "VOUT_5") (pintype "bidirectional"))
      (node (ref "U6") (pin "10") (pinfunction "VDD_IO_10") (pintype "power_in"))
      (node (ref "U6") (pin "2") (pinfunction "CS_2") (pintype "input"))
      (node (ref "U6") (pin "9") (pinfunction "VDD_9") (pintype "power_in"))
      (node (ref "U9") (pin "6") (pinfunction "VDD_6") (pintype "power_in"))
      (node (ref "U9") (pin "7") (pinfunction "VREGIN_7") (pintype "power_in"))
      (node (ref "X1") (pin "1") (pinfunction "B_1") (pintype "passive"))
    )
    (net (code "56") (name "unconnected-(J1-CC1-PadA5)") (class "Default")
      (node (ref "J1") (pin "A5") (pinfunction "CC1_A5") (pintype "bidirectional"))
    )
    (net (code "57") (name "unconnected-(J1-CC2-PadB5)") (class "Default")
      (node (ref "J1") (pin "B5") (pinfunction "CC2_B5") (pintype "bidirectional"))
    )
    (net (code "58") (name "unconnected-(J1-SBU1-PadA8)") (class "Default")
      (node (ref "J1") (pin "A8") (pinfunction "SBU1_A8") (pintype "bidirectional"))
    )
    (net (code "59") (name "unconnected-(J1-SBU2-PadB8)") (class "Default")
      (node (ref "J1") (pin "B8") (pinfunction "SBU2_B8") (pintype "bidirectional"))
    )
    (net (code "60") (name "unconnected-(U$1-3V3-PadP$16)") (class "Default")
      (node (ref "U$1") (pin "P$16") (pinfunction "3V3_P$16") (pintype "bidirectional"))
    )
    (net (code "61") (name "unconnected-(U$1-3V3.-PadP$12)") (class "Default")
      (node (ref "U$1") (pin "P$12") (pinfunction "3V3._P$12") (pintype "bidirectional"))
    )
    (net (code "62") (name "unconnected-(U1-PA00-Pad25)") (class "Default")
      (node (ref "U1") (pin "25") (pinfunction "PA00_25") (pintype "bidirectional"))
    )
    (net (code "63") (name "unconnected-(U1-PA08-Pad33)") (class "Default")
      (node (ref "U1") (pin "33") (pinfunction "PA08_33") (pintype "bidirectional"))
    )
    (net (code "64") (name "unconnected-(U1-PA09-Pad34)") (class "Default")
      (node (ref "U1") (pin "34") (pinfunction "PA09_34") (pintype "bidirectional"))
    )
    (net (code "65") (name "unconnected-(U1-PA10-Pad35)") (class "Default")
      (node (ref "U1") (pin "35") (pinfunction "PA10_35") (pintype "bidirectional"))
    )
    (net (code "66") (name "unconnected-(U1-PB00-Pad24)") (class "Default")
      (node (ref "U1") (pin "24") (pinfunction "PB00_24") (pintype "bidirectional"))
    )
    (net (code "67") (name "unconnected-(U1-PB01-Pad23)") (class "Default")
      (node (ref "U1") (pin "23") (pinfunction "PB01_23") (pintype "bidirectional"))
    )
    (net (code "68") (name "unconnected-(U1-PB02-Pad22)") (class "Default")
      (node (ref "U1") (pin "22") (pinfunction "PB02_22") (pintype "bidirectional"))
    )
    (net (code "69") (name "unconnected-(U1-PB03-Pad21)") (class "Default")
      (node (ref "U1") (pin "21") (pinfunction "PB03_21") (pintype "bidirectional"))
    )
    (net (code "70") (name "unconnected-(U1-PC00-Pad1)") (class "Default")
      (node (ref "U1") (pin "1") (pinfunction "PC00_1") (pintype "bidirectional"))
    )
    (net (code "71") (name "unconnected-(U1-PC01-Pad2)") (class "Default")
      (node (ref "U1") (pin "2") (pinfunction "PC01_2") (pintype "bidirectional"))
    )
    (net (code "72") (name "unconnected-(U1-PC04-Pad5)") (class "Default")
      (node (ref "U1") (pin "5") (pinfunction "PC04_5") (pintype "bidirectional"))
    )
    (net (code "73") (name "unconnected-(U1-PC05-Pad6)") (class "Default")
      (node (ref "U1") (pin "6") (pinfunction "PC05_6") (pintype "bidirectional"))
    )
    (net (code "74") (name "unconnected-(U1-PC06-Pad7)") (class "Default")
      (node (ref "U1") (pin "7") (pinfunction "PC06_7") (pintype "bidirectional"))
    )
    (net (code "75") (name "unconnected-(U1-PC07-Pad8)") (class "Default")
      (node (ref "U1") (pin "8") (pinfunction "PC07_8") (pintype "bidirectional"))
    )
    (net (code "76") (name "unconnected-(U1-PC08-Pad9)") (class "Default")
      (node (ref "U1") (pin "9") (pinfunction "PC08_9") (pintype "bidirectional"))
    )
    (net (code "77") (name "unconnected-(U1-PC09-Pad10)") (class "Default")
      (node (ref "U1") (pin "10") (pinfunction "PC09_10") (pintype "bidirectional"))
    )
    (net (code "78") (name "unconnected-(U1-PD02-Pad46)") (class "Default")
      (node (ref "U1") (pin "46") (pinfunction "PD02_46") (pintype "bidirectional"))
    )
    (net (code "79") (name "unconnected-(U1-PD03-Pad45)") (class "Default")
      (node (ref "U1") (pin "45") (pinfunction "PD03_45") (pintype "bidirectional"))
    )
    (net (code "80") (name "unconnected-(U1-PD04-Pad44)") (class "Default")
      (node (ref "U1") (pin "44") (pinfunction "PD04_44") (pintype "bidirectional"))
    )
    (net (code "81") (name "unconnected-(U1-PD05-Pad43)") (class "Default")
      (node (ref "U1") (pin "43") (pinfunction "PD05_43") (pintype "bidirectional"))
    )
    (net (code "82") (name "unconnected-(U1-SUBG_I1-Pad16)") (class "Default")
      (node (ref "U1") (pin "16") (pinfunction "SUBG_I1_16") (pintype "input"))
    )
    (net (code "83") (name "unconnected-(U1-SUBG_O1-Pad18)") (class "Default")
      (node (ref "U1") (pin "18") (pinfunction "SUBG_O1_18") (pintype "output"))
    )
    (net (code "84") (name "unconnected-(U3-GPIO1-Pad7)") (class "Default")
      (node (ref "U3") (pin "7") (pinfunction "GPIO1_7") (pintype "output"))
    )
    (net (code "85") (name "unconnected-(U5-LOAD-Pad6)") (class "Default")
      (node (ref "U5") (pin "6") (pinfunction "LOAD_6") (pintype "bidirectional"))
    )
    (net (code "86") (name "unconnected-(U5-PG-Pad7)") (class "Default")
      (node (ref "U5") (pin "7") (pinfunction "PG_7") (pintype "bidirectional"))
    )
    (net (code "87") (name "unconnected-(U6-INT2-Pad11)") (class "Default")
      (node (ref "U6") (pin "11") (pinfunction "INT2_11") (pintype "output"))
    )
    (net (code "88") (name "unconnected-(U9A-CHR0-Pad15)") (class "Default")
      (node (ref "U9") (pin "15") (pinfunction "CHR0_15") (pintype "output"))
    )
    (net (code "89") (name "unconnected-(U9A-CHR1-Pad14)") (class "Default")
      (node (ref "U9") (pin "14") (pinfunction "CHR1_14") (pintype "output"))
    )
    (net (code "90") (name "unconnected-(U9A-CHREN-Pad13)") (class "Default")
      (node (ref "U9") (pin "13") (pinfunction "CHREN_13") (pintype "output"))
    )
    (net (code "91") (name "unconnected-(U9A-CTS-Pad23)") (class "Default")
      (node (ref "U9") (pin "23") (pinfunction "CTS_23") (pintype "input"))
    )
    (net (code "92") (name "unconnected-(U9A-DCD-Pad1)") (class "Default")
      (node (ref "U9") (pin "1") (pinfunction "DCD_1") (pintype "input"))
    )
    (net (code "93") (name "unconnected-(U9A-DSR-Pad27)") (class "Default")
      (node (ref "U9") (pin "27") (pinfunction "DSR_27") (pintype "input"))
    )
    (net (code "94") (name "unconnected-(U9A-GPIO.0{slash}TXT-Pad19)") (class "Default")
      (node (ref "U9") (pin "19") (pinfunction "GPIO.0/TXT_19") (pintype "bidirectional"))
    )
    (net (code "95") (name "unconnected-(U9A-GPIO.1{slash}RXT-Pad18)") (class "Default")
      (node (ref "U9") (pin "18") (pinfunction "GPIO.1/RXT_18") (pintype "bidirectional"))
    )
    (net (code "96") (name "unconnected-(U9A-GPIO.2{slash}RS485-Pad17)") (class "Default")
      (node (ref "U9") (pin "17") (pinfunction "GPIO.2/RS485_17") (pintype "bidirectional"))
    )
    (net (code "97") (name "unconnected-(U9A-GPIO.3{slash}WAKEUP-Pad16)") (class "Default")
      (node (ref "U9") (pin "16") (pinfunction "GPIO.3/WAKEUP_16") (pintype "bidirectional"))
    )
    (net (code "98") (name "unconnected-(U9A-GPIO.4-Pad22)") (class "Default")
      (node (ref "U9") (pin "22") (pinfunction "GPIO.4_22") (pintype "bidirectional"))
    )
    (net (code "99") (name "unconnected-(U9A-GPIO.5-Pad21)") (class "Default")
      (node (ref "U9") (pin "21") (pinfunction "GPIO.5_21") (pintype "bidirectional"))
    )
    (net (code "100") (name "unconnected-(U9A-GPIO.6-Pad20)") (class "Default")
      (node (ref "U9") (pin "20") (pinfunction "GPIO.6_20") (pintype "bidirectional"))
    )
    (net (code "101") (name "unconnected-(U9A-RI{slash}CLK-Pad2)") (class "Default")
      (node (ref "U9") (pin "2") (pinfunction "RI/CLK_2") (pintype "bidirectional"))
    )
    (net (code "102") (name "unconnected-(U9A-SUSPEND-Pad12)") (class "Default")
      (node (ref "U9") (pin "12") (pinfunction "SUSPEND_12") (pintype "output"))
    )
    (net (code "103") (name "unconnected-(U9A-SUSPENDB-Pad11)") (class "Default")
      (node (ref "U9") (pin "11") (pinfunction "SUSPENDB_11") (pintype "output"))
    )
    (net (code "104") (name "unconnected-(U9B-NC-Pad10)") (class "Default")
      (node (ref "U9") (pin "10") (pinfunction "NC_10") (pintype "no_connect"))
    )
    (net (code "105") (name "unconnected-(U13-DO-Pad1)") (class "Default")
      (node (ref "U13") (pin "1") (pinfunction "DO_1") (pintype "output"))
    )
  )
)
